# SCH_Driver_Key_1_3-PCB_2026-04-09.net
KiCad netlist of a schematic drawn in EasyEDA
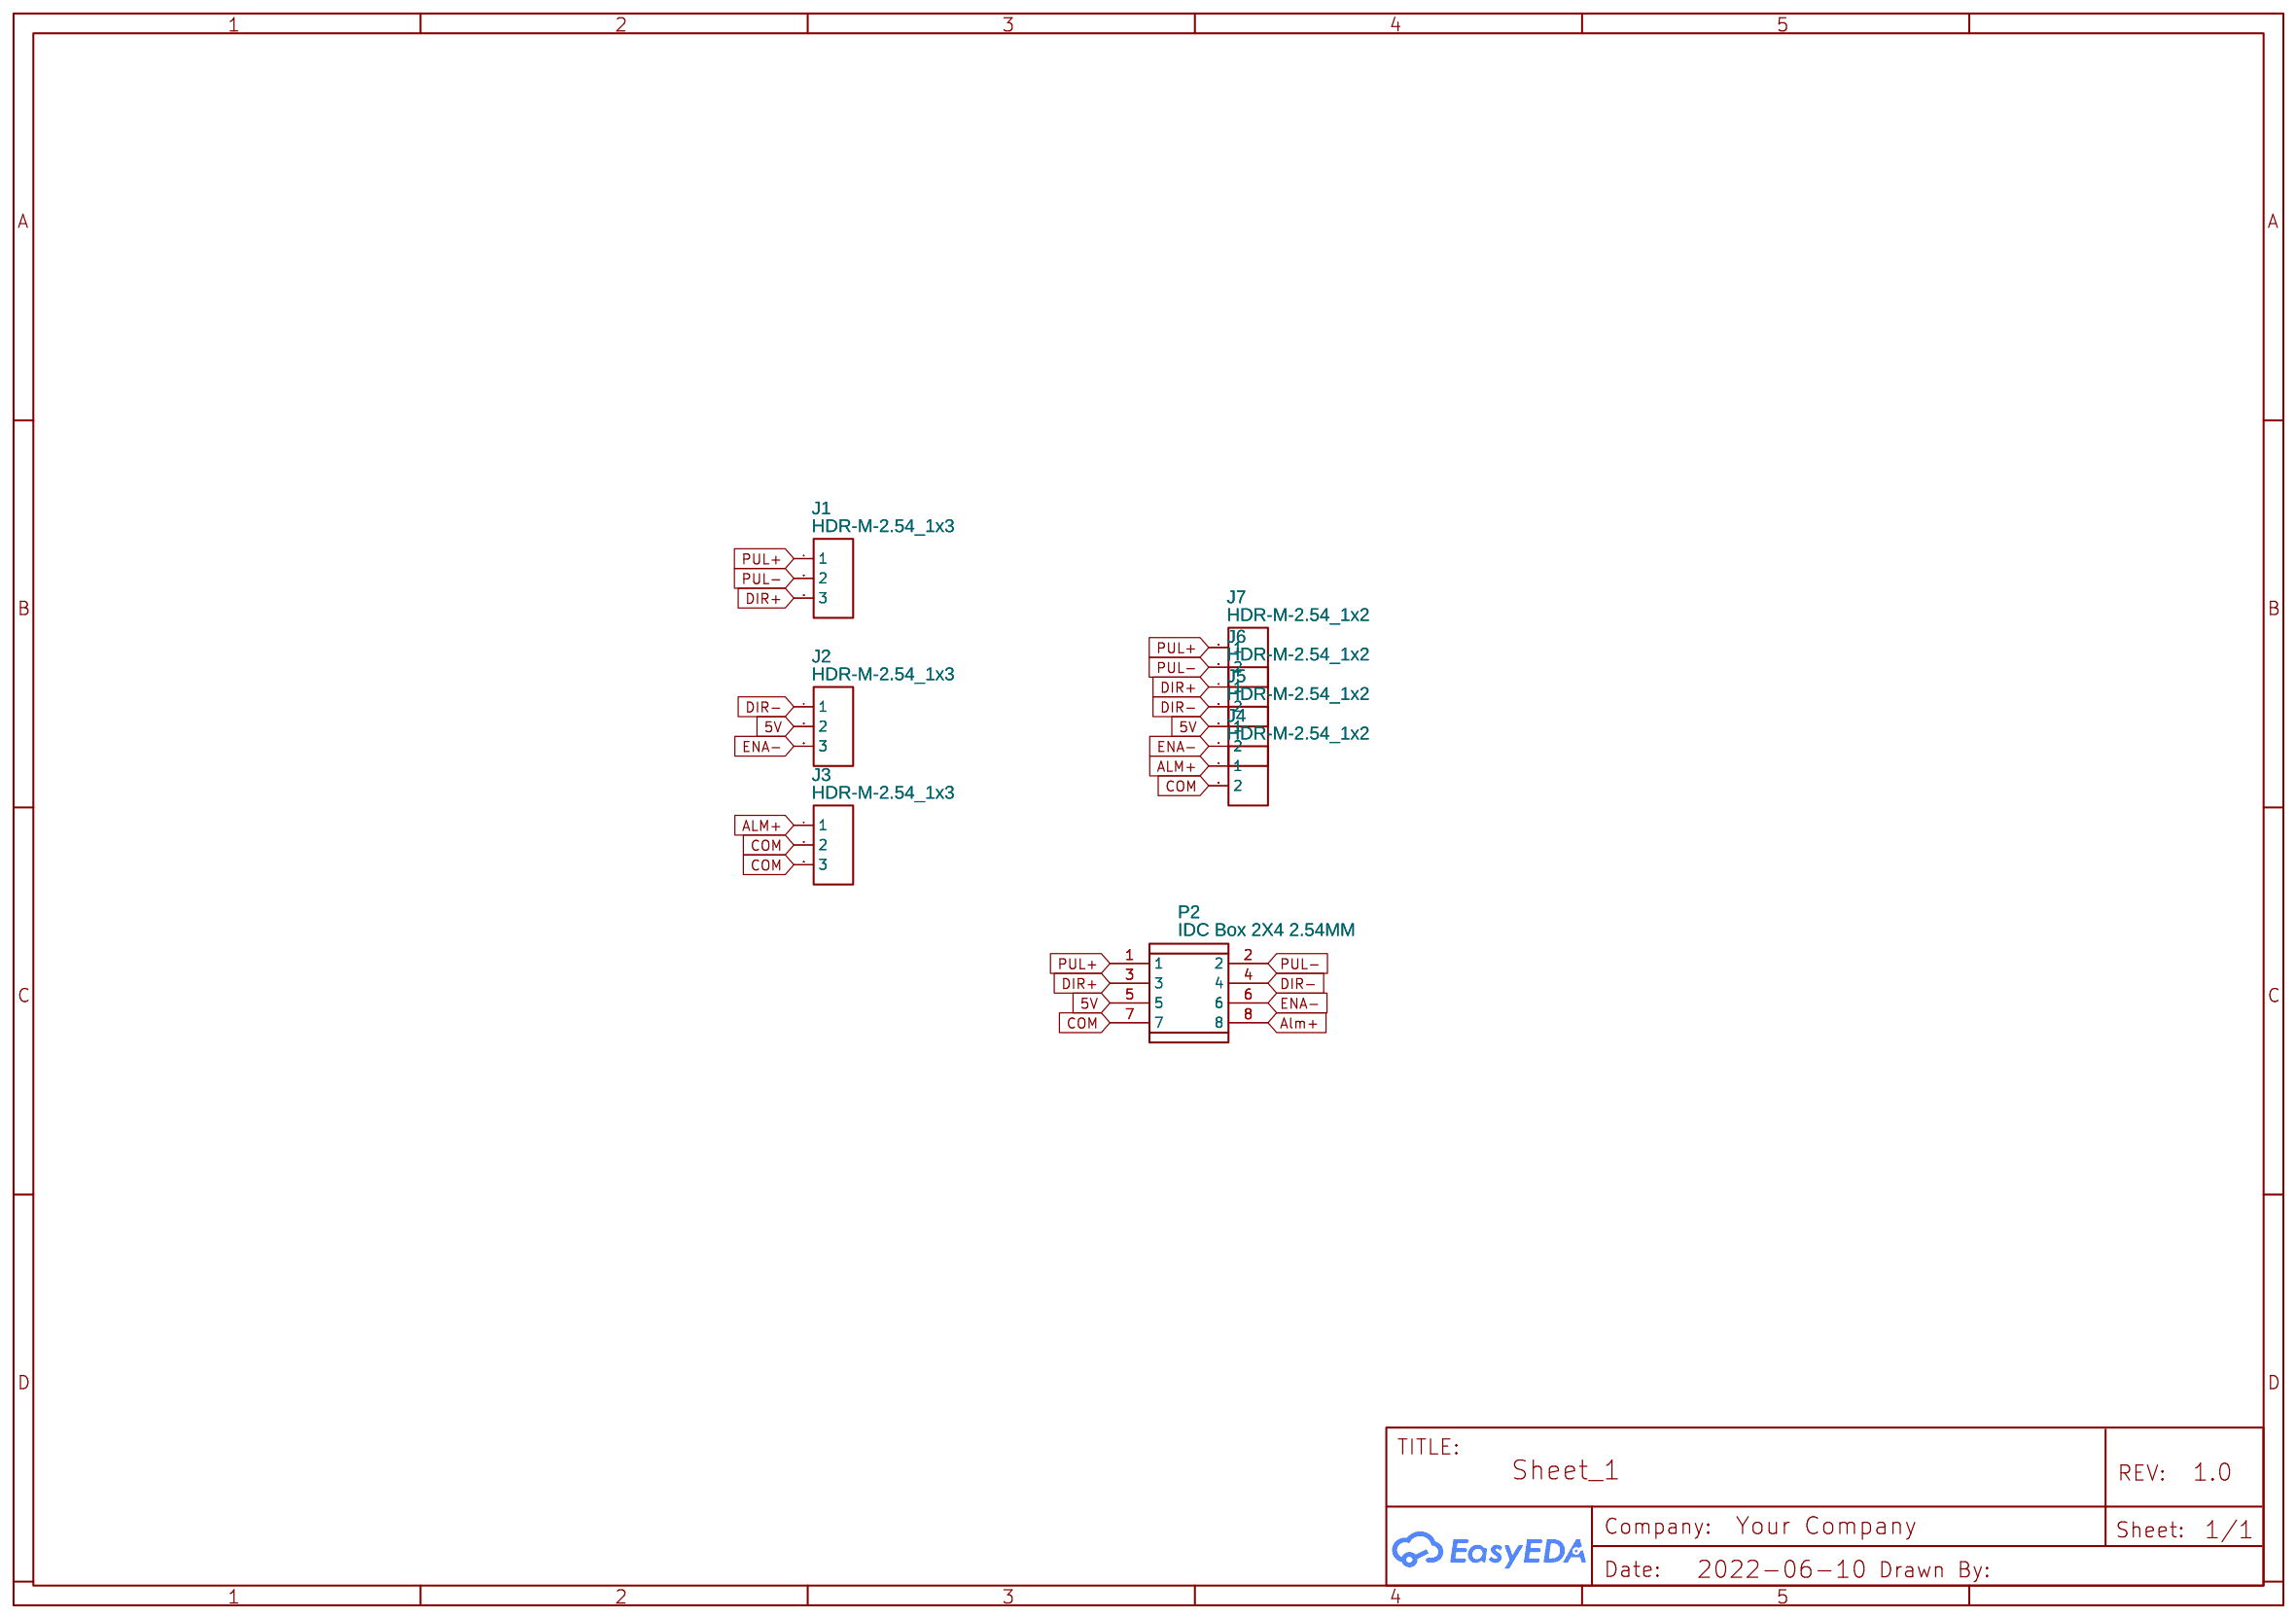
[diagram p0: schematic sheet]

(export (version "E")
  (design (tool "Eeschema 10.0.6"))
  (components
    (comp (ref "J1") (value "HDR-M-2.54_1x3") (libsource (lib "") (part "HDR-M-2.54_1x3")))
    (comp (ref "J2") (value "HDR-M-2.54_1x3") (libsource (lib "") (part "HDR-M-2.54_1x3")))
    (comp (ref "J3") (value "HDR-M-2.54_1x3") (libsource (lib "") (part "HDR-M-2.54_1x3")))
    (comp (ref "J4") (value "HDR-M-2.54_1x2") (libsource (lib "") (part "HDR-M-2.54_1x2")))
    (comp (ref "J5") (value "HDR-M-2.54_1x2") (libsource (lib "") (part "HDR-M-2.54_1x2")))
    (comp (ref "J6") (value "HDR-M-2.54_1x2") (libsource (lib "") (part "HDR-M-2.54_1x2")))
    (comp (ref "J7") (value "HDR-M-2.54_1x2") (libsource (lib "") (part "HDR-M-2.54_1x2")))
    (comp (ref "P2")
      (value "IDC Box 2X4 2.54MM")
      (fields (field (name "Manufacturer Part") "2.54-2*4P弯简牛") (field (name "Manufacturer") "BOOMELE(博穆精密)"))
      (libsource (lib "") (part "IDC Box 2X4 2.54MM"))
    )
  )
  (nets
    (net (code "1") (name "5V") (class "Default")
      (node (ref "J2") (pin "2") (pinfunction "2_2") (pintype "input"))
      (node (ref "J5") (pin "1") (pinfunction "1_1") (pintype "unspecified"))
      (node (ref "P2") (pin "5") (pinfunction "5_5") (pintype "unspecified"))
    )
    (net (code "2") (name "ALM+") (class "Default")
      (node (ref "J3") (pin "1") (pinfunction "1_1") (pintype "input"))
      (node (ref "J4") (pin "1") (pinfunction "1_1") (pintype "unspecified"))
    )
    (net (code "3") (name "Alm+") (class "Default")
      (node (ref "P2") (pin "8") (pinfunction "8_8") (pintype "unspecified"))
    )
    (net (code "4") (name "COM") (class "Default")
      (node (ref "J3") (pin "2") (pinfunction "2_2") (pintype "input"))
      (node (ref "J3") (pin "3") (pinfunction "3_3") (pintype "input"))
      (node (ref "J4") (pin "2") (pinfunction "2_2") (pintype "unspecified"))
      (node (ref "P2") (pin "7") (pinfunction "7_7") (pintype "unspecified"))
    )
    (net (code "5") (name "DIR+") (class "Default")
      (node (ref "J1") (pin "3") (pinfunction "3_3") (pintype "input"))
      (node (ref "J6") (pin "1") (pinfunction "1_1") (pintype "unspecified"))
      (node (ref "P2") (pin "3") (pinfunction "3_3") (pintype "unspecified"))
    )
    (net (code "6") (name "DIR-") (class "Default")
      (node (ref "J2") (pin "1") (pinfunction "1_1") (pintype "input"))
      (node (ref "J6") (pin "2") (pinfunction "2_2") (pintype "unspecified"))
      (node (ref "P2") (pin "4") (pinfunction "4_4") (pintype "unspecified"))
    )
    (net (code "7") (name "ENA-") (class "Default")
      (node (ref "J2") (pin "3") (pinfunction "3_3") (pintype "input"))
      (node (ref "J5") (pin "2") (pinfunction "2_2") (pintype "unspecified"))
      (node (ref "P2") (pin "6") (pinfunction "6_6") (pintype "unspecified"))
    )
    (net (code "8") (name "PUL+") (class "Default")
      (node (ref "J1") (pin "1") (pinfunction "1_1") (pintype "input"))
      (node (ref "J7") (pin "1") (pinfunction "1_1") (pintype "unspecified"))
      (node (ref "P2") (pin "1") (pinfunction "1_1") (pintype "unspecified"))
    )
    (net (code "9") (name "PUL-") (class "Default")
      (node (ref "J1") (pin "2") (pinfunction "2_2") (pintype "input"))
      (node (ref "J7") (pin "2") (pinfunction "2_2") (pintype "unspecified"))
      (node (ref "P2") (pin "2") (pinfunction "2_2") (pintype "unspecified"))
    )
  )
)
